# 6.net
KiCad netlist of a schematic drawn in Altium Designer
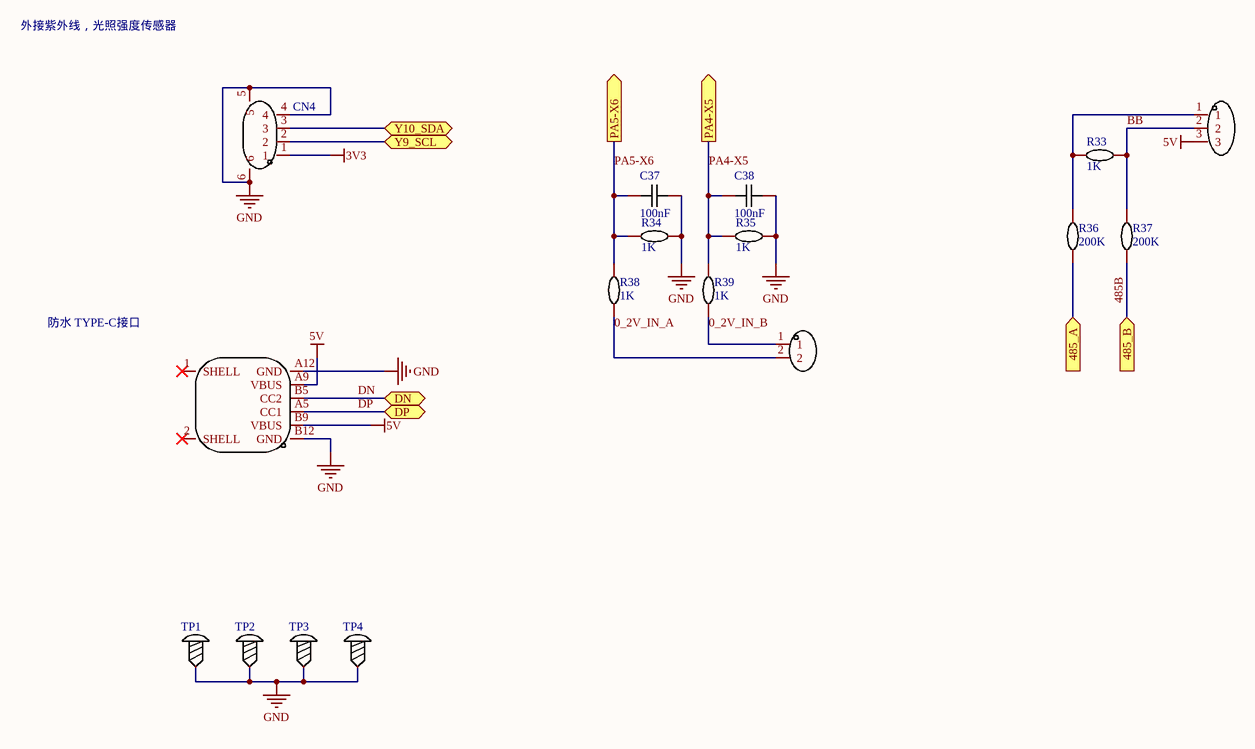
[diagram p0: 6_对外接口.Schdoc]

(export (version "E")
  (design (tool "Eeschema 10.0.6"))
  (components
    (comp (ref "C37")
      (value "100nF")
      (footprint "0402")
      (fields (field (name "NAME") "100nF"))
      (libsource (lib "1_对外接口.schdoc") (part "CAP_0402"))
    )
    (comp (ref "C38")
      (value "100nF")
      (footprint "0402")
      (fields (field (name "NAME") "100nF"))
      (libsource (lib "1_对外接口.schdoc") (part "CAP_0402"))
    )
    (comp (ref "CN4")
      (value "HX25003-4AWB")
      (footprint "CONN-SMD_4P-P2.50_HX25003-4AWB")
      (libsource (lib "1_对外接口.schdoc") (part "HX25003-4AWB"))
    )
    (comp (ref "CN5")
      (value "XH-3A")
      (footprint "CONN-TH_XH-3A")
      (libsource (lib "XH-3A_C29086011_XH-3A_C2908601.schdoc") (part "XH-3A"))
    )
    (comp (ref "CN6")
      (value "XH-2A")
      (footprint "CONN-TH_2P-P2.50_HCTL_XH-2A-X")
      (libsource (lib "XH-2A_C29086001_XH-2A_C2908600.schdoc") (part "XH-2A"))
    )
    (comp (ref "R33")
      (value "1K")
      (footprint "0603R")
      (fields (field (name "NAME") "1K"))
      (libsource (lib "1_对外接口.schdoc") (part "Res_0603"))
    )
    (comp (ref "R34")
      (value "1K")
      (footprint "0603R")
      (fields (field (name "NAME") "1K"))
      (libsource (lib "1_对外接口.schdoc") (part "Res_0603"))
    )
    (comp (ref "R35")
      (value "1K")
      (footprint "0603R")
      (fields (field (name "NAME") "1K"))
      (libsource (lib "1_对外接口.schdoc") (part "Res_0603"))
    )
    (comp (ref "R36")
      (value "200K")
      (footprint "0805")
      (fields (field (name "NAME") "200K"))
      (libsource (lib "1_对外接口.schdoc") (part "Res_0805"))
    )
    (comp (ref "R37")
      (value "200K")
      (footprint "0805")
      (fields (field (name "NAME") "200K"))
      (libsource (lib "1_对外接口.schdoc") (part "Res_0805"))
    )
    (comp (ref "R38")
      (value "1K")
      (footprint "0603R")
      (fields (field (name "NAME") "1K"))
      (libsource (lib "1_对外接口.schdoc") (part "Res_0603"))
    )
    (comp (ref "R39")
      (value "1K")
      (footprint "0603R")
      (fields (field (name "NAME") "1K"))
      (libsource (lib "1_对外接口.schdoc") (part "Res_0603"))
    )
    (comp (ref "TP1")
      (value "M3__")
      (footprint "PCBComponent_1 - duplicate")
      (libsource (lib "1_对外接口.schdoc") (part "M3__"))
    )
    (comp (ref "TP2")
      (value "M3__")
      (footprint "PCBComponent_1 - duplicate")
      (libsource (lib "1_对外接口.schdoc") (part "M3__"))
    )
    (comp (ref "TP3")
      (value "M3__")
      (footprint "PCBComponent_1 - duplicate")
      (libsource (lib "1_对外接口.schdoc") (part "M3__"))
    )
    (comp (ref "TP4")
      (value "M3__")
      (footprint "PCBComponent_1 - duplicate")
      (libsource (lib "1_对外接口.schdoc") (part "M3__"))
    )
    (comp (ref "USB2")
      (value "TYPE-C 6P(040_)")
      (footprint "USB-C-SMD_TYPE-C-6P")
      (libsource (lib "TYPE-C 6P(040新)1_TYPE-C 6P(040新).schdoc") (part "TYPE-C 6P(040_)"))
    )
  )
  (nets
    (net (code "1") (name "/0_2V_IN_A") (class "Default")
      (node (ref "CN6") (pin "2") (pinfunction "2_2") (pintype "passive"))
      (node (ref "R38") (pin "1") (pinfunction "1_1") (pintype "passive"))
    )
    (net (code "2") (name "/0_2V_IN_B") (class "Default")
      (node (ref "CN6") (pin "1") (pinfunction "1_1") (pintype "passive"))
      (node (ref "R39") (pin "1") (pinfunction "1_1") (pintype "passive"))
    )
    (net (code "3") (name "/485B") (class "Default")
      (node (ref "R37") (pin "1") (pinfunction "1_1") (pintype "passive"))
    )
    (net (code "4") (name "/485_A") (class "Default")
      (node (ref "R36") (pin "1") (pinfunction "1_1") (pintype "passive"))
    )
    (net (code "5") (name "/BB") (class "Default")
      (node (ref "CN5") (pin "2") (pinfunction "2_2") (pintype "passive"))
      (node (ref "R33") (pin "2") (pinfunction "2_2") (pintype "passive"))
      (node (ref "R37") (pin "2") (pinfunction "2_2") (pintype "passive"))
    )
    (net (code "6") (name "/DN") (class "Default")
      (node (ref "USB2") (pin "B5") (pinfunction "CC2_B5") (pintype "passive"))
    )
    (net (code "7") (name "/DP") (class "Default")
      (node (ref "USB2") (pin "A5") (pinfunction "CC1_A5") (pintype "passive"))
    )
    (net (code "8") (name "/PA4-X5") (class "Default")
      (node (ref "C38") (pin "1") (pinfunction "1_1") (pintype "passive"))
      (node (ref "R35") (pin "2") (pinfunction "2_2") (pintype "passive"))
      (node (ref "R39") (pin "2") (pinfunction "2_2") (pintype "passive"))
    )
    (net (code "9") (name "/PA5-X6") (class "Default")
      (node (ref "C37") (pin "1") (pinfunction "1_1") (pintype "passive"))
      (node (ref "R34") (pin "2") (pinfunction "2_2") (pintype "passive"))
      (node (ref "R38") (pin "2") (pinfunction "2_2") (pintype "passive"))
    )
    (net (code "10") (name "/Y9_SCL") (class "Default")
      (node (ref "CN4") (pin "2") (pinfunction "2_2") (pintype "passive"))
    )
    (net (code "11") (name "/Y10_SDA") (class "Default")
      (node (ref "CN4") (pin "3") (pinfunction "3_3") (pintype "passive"))
    )
    (net (code "12") (name "3V3") (class "Default")
      (node (ref "CN4") (pin "1") (pinfunction "1_1") (pintype "passive"))
    )
    (net (code "13") (name "5V") (class "Default")
      (node (ref "CN5") (pin "3") (pinfunction "3_3") (pintype "passive"))
      (node (ref "USB2") (pin "A9") (pinfunction "VBUS_A9") (pintype "passive"))
      (node (ref "USB2") (pin "B9") (pinfunction "VBUS_B9") (pintype "passive"))
    )
    (net (code "14") (name "GND") (class "Default")
      (node (ref "C37") (pin "2") (pinfunction "2_2") (pintype "passive"))
      (node (ref "C38") (pin "2") (pinfunction "2_2") (pintype "passive"))
      (node (ref "CN4") (pin "4") (pinfunction "4_4") (pintype "passive"))
      (node (ref "CN4") (pin "5") (pinfunction "5_5") (pintype "passive"))
      (node (ref "CN4") (pin "6") (pinfunction "6_6") (pintype "passive"))
      (node (ref "R34") (pin "1") (pinfunction "1_1") (pintype "passive"))
      (node (ref "R35") (pin "1") (pinfunction "1_1") (pintype "passive"))
      (node (ref "TP1") (pin "1") (pinfunction "1_1") (pintype "passive"))
      (node (ref "TP2") (pin "1") (pinfunction "1_1") (pintype "passive"))
      (node (ref "TP3") (pin "1") (pinfunction "1_1") (pintype "passive"))
      (node (ref "TP4") (pin "1") (pinfunction "1_1") (pintype "passive"))
      (node (ref "USB2") (pin "A12") (pinfunction "GND_A12") (pintype "passive"))
      (node (ref "USB2") (pin "B12") (pinfunction "GND_B12") (pintype "passive"))
    )
    (net (code "15") (name "Net-(CN5-Pad1)") (class "Default")
      (node (ref "CN5") (pin "1") (pinfunction "1_1") (pintype "passive"))
      (node (ref "R33") (pin "1") (pinfunction "1_1") (pintype "passive"))
      (node (ref "R36") (pin "2") (pinfunction "2_2") (pintype "passive"))
    )
    (net (code "16") (name "unconnected-(USB2-SHELL-Pad1)") (class "Default")
      (node (ref "USB2") (pin "1") (pinfunction "SHELL_1") (pintype "passive+no_connect"))
    )
    (net (code "17") (name "unconnected-(USB2-SHELL-Pad2)") (class "Default")
      (node (ref "USB2") (pin "2") (pinfunction "SHELL_2") (pintype "passive+no_connect"))
    )
  )
)
